# laserTarget.net
KiCad netlist of a schematic drawn in EAGLE
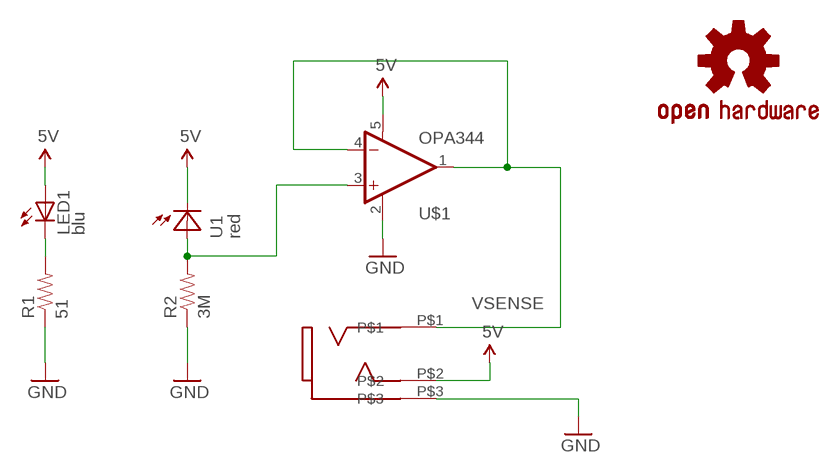
[diagram p0: schematic, sheet 1]

(export (version "E")
  (design (tool "Eeschema 10.0.6"))
  (components
    (comp (ref "LED1")
      (value "blu")
      (footprint "eagle-import:LED5MM")
      (libsource (lib "eagle-import") (part "LED5MM"))
    )
    (comp (ref "LOGO1")
      (value "OSHW-LOGOS")
      (footprint "eagle-import:OSHW-LOGO-S")
      (libsource (lib "eagle-import") (part "OSHW-LOGOS"))
    )
    (comp (ref "R1")
      (value "51")
      (footprint "eagle-import:0805")
      (libsource (lib "eagle-import") (part "RESISTOR0805-RES"))
    )
    (comp (ref "R2")
      (value "3M")
      (footprint "eagle-import:0805")
      (libsource (lib "eagle-import") (part "RESISTOR0805-RES"))
    )
    (comp (ref "U$1")
      (value "OPA344")
      (footprint "eagle-import:SOT23-5")
      (libsource (lib "eagle-import") (part "OPA344"))
    )
    (comp (ref "U$2")
      (value "35RASMT2BHNTRX")
      (footprint "eagle-import:35RASMT2BHNTRX")
      (libsource (lib "eagle-import") (part "35RASMT2BHNTRX"))
    )
    (comp (ref "U1")
      (value "red")
      (footprint "eagle-import:CLS15")
      (libsource (lib "eagle-import") (part "CLS15CLS15"))
    )
  )
  (nets
    (net (code "1") (name "/VSENSE") (class "Default")
      (node (ref "U$1") (pin "1") (pinfunction "OUT_1") (pintype "output"))
      (node (ref "U$1") (pin "4") (pinfunction "-IN_4") (pintype "input"))
      (node (ref "U$2") (pin "P$1") (pinfunction "P$1_P$1") (pintype "bidirectional"))
    )
    (net (code "2") (name "5V") (class "Default")
      (node (ref "LED1") (pin "A") (pinfunction "A_A") (pintype "passive"))
      (node (ref "U$1") (pin "5") (pinfunction "V+_5") (pintype "power_in"))
      (node (ref "U$2") (pin "P$2") (pinfunction "P$2_P$2") (pintype "bidirectional"))
      (node (ref "U1") (pin "3") (pinfunction "C_3") (pintype "passive"))
      (node (ref "U1") (pin "4") (pinfunction "C_4") (pintype "passive"))
    )
    (net (code "3") (name "GND") (class "Default")
      (node (ref "R1") (pin "1") (pinfunction "1_1") (pintype "passive"))
      (node (ref "R2") (pin "1") (pinfunction "1_1") (pintype "passive"))
      (node (ref "U$1") (pin "2") (pinfunction "V-_2") (pintype "power_in"))
      (node (ref "U$2") (pin "P$3") (pinfunction "P$3_P$3") (pintype "bidirectional"))
    )
    (net (code "4") (name "Net-(LED1-C)") (class "Default")
      (node (ref "LED1") (pin "K") (pinfunction "C_K") (pintype "passive"))
      (node (ref "R1") (pin "2") (pinfunction "2_2") (pintype "passive"))
    )
    (net (code "5") (name "Net-(U$1-+IN)") (class "Default")
      (node (ref "R2") (pin "2") (pinfunction "2_2") (pintype "passive"))
      (node (ref "U$1") (pin "3") (pinfunction "+IN_3") (pintype "input"))
      (node (ref "U1") (pin "1") (pinfunction "A_1") (pintype "passive"))
      (node (ref "U1") (pin "2") (pinfunction "A_2") (pintype "passive"))
    )
  )
)
